# serialLogger.net
KiCad netlist of a schematic drawn in EAGLE
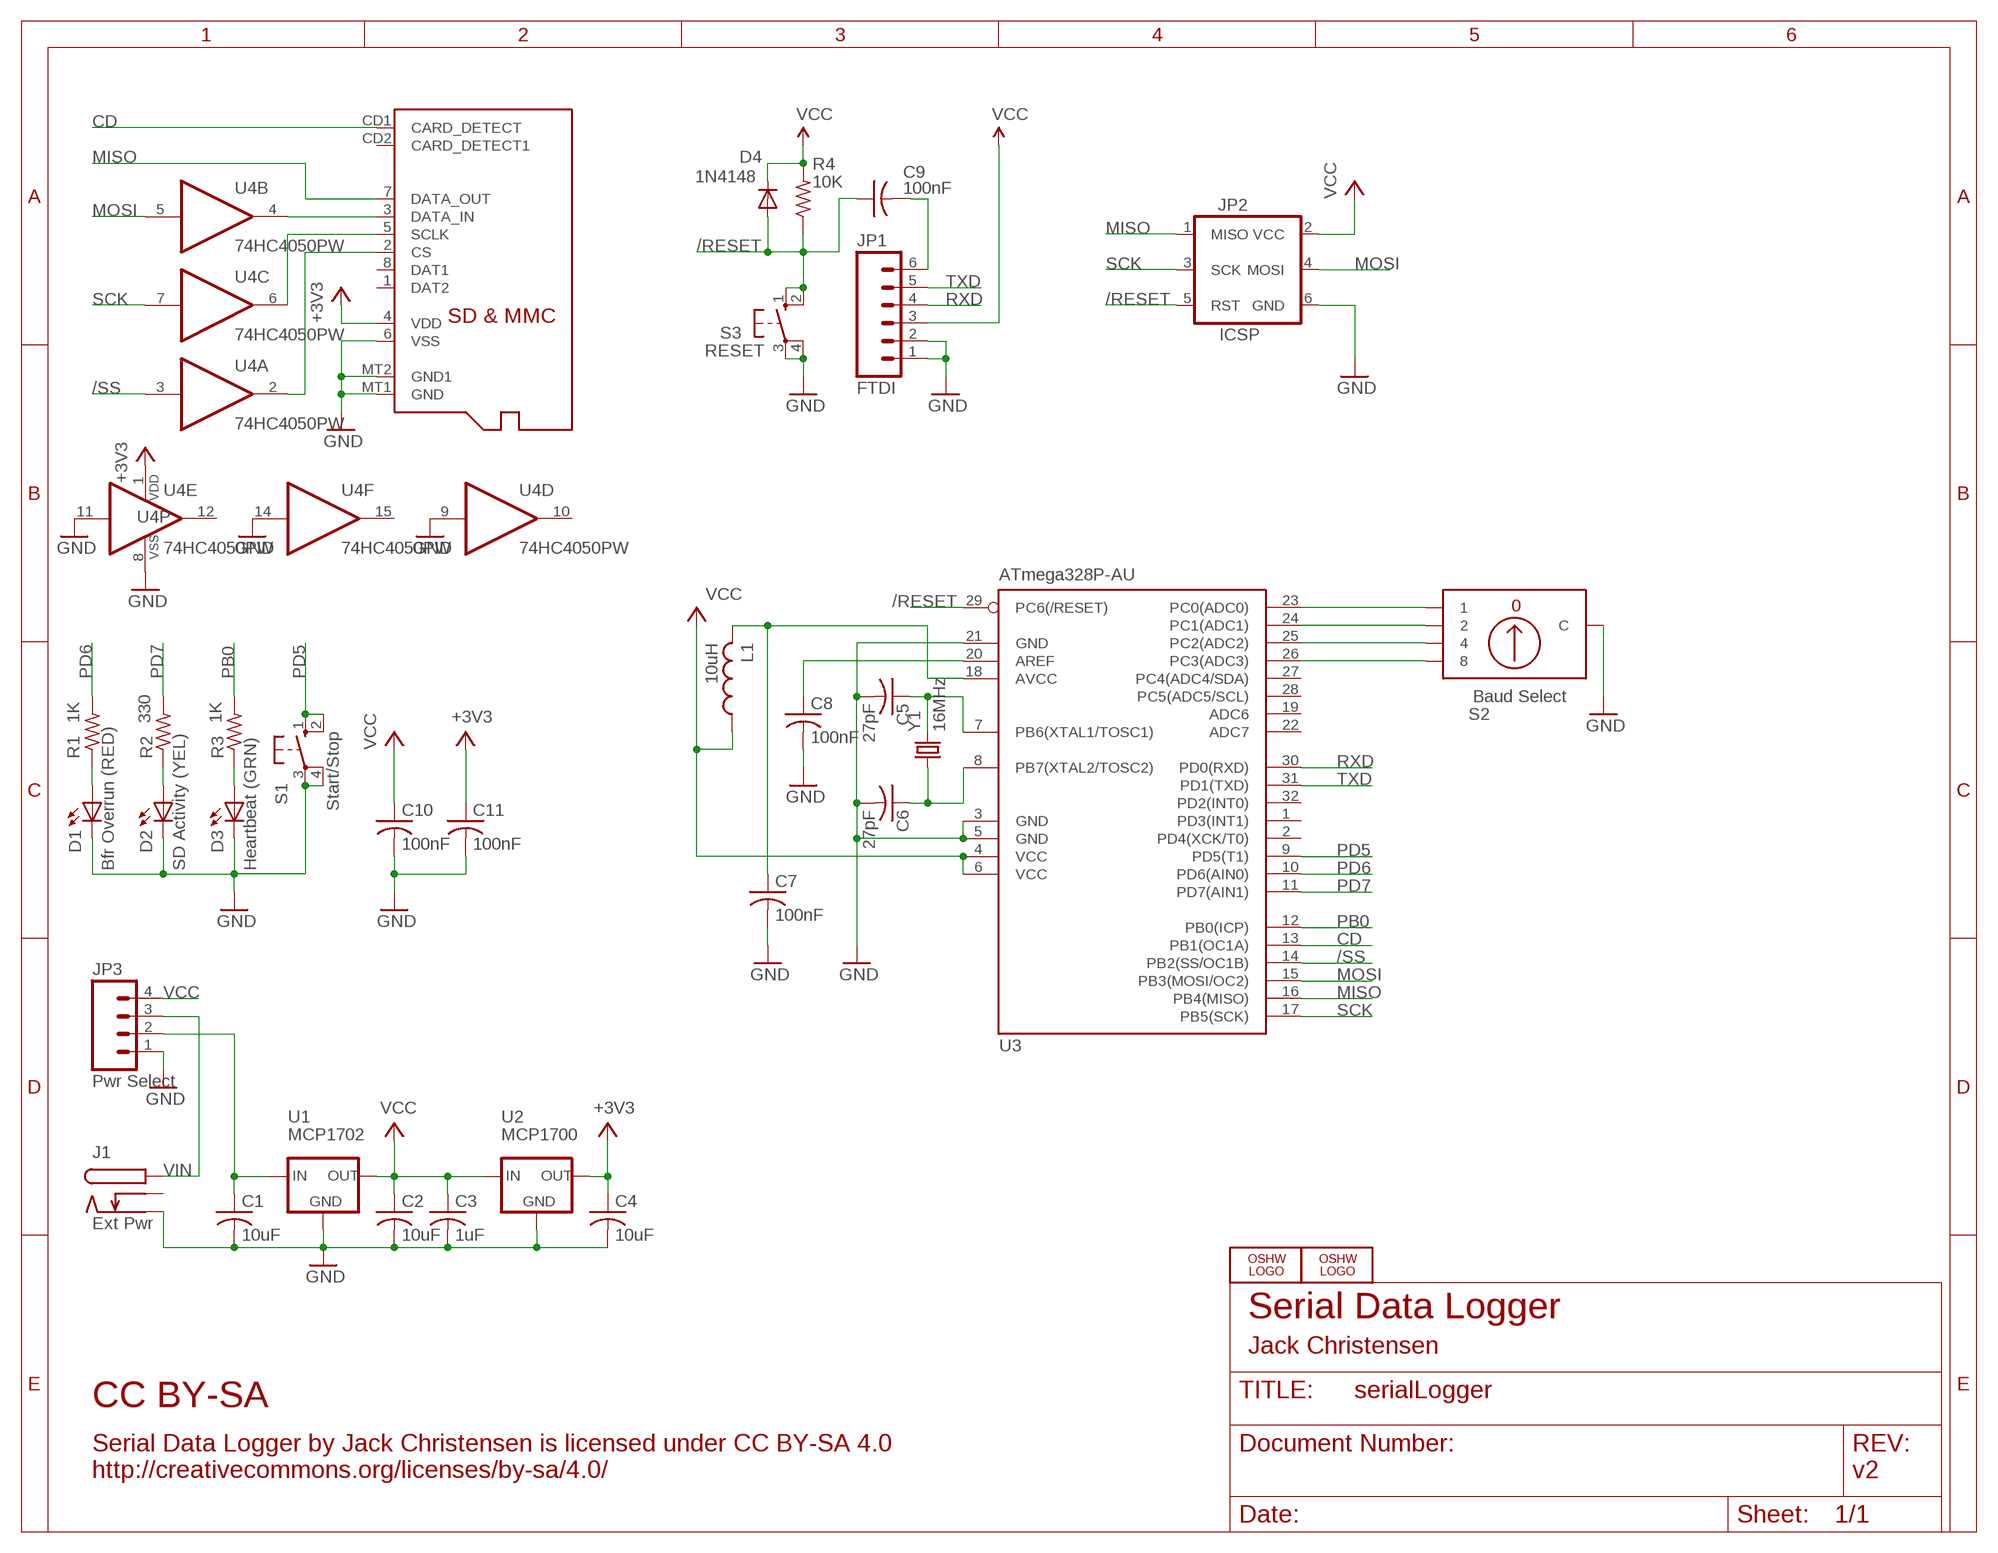
[diagram p0: schematic, sheet 1]

(export (version "E")
  (design (tool "Eeschema 10.0.6"))
  (components
    (comp (ref "C1")
      (value "10uF")
      (footprint "eagle-import:M0805")
      (libsource (lib "eagle-import") (part "C-USM0805"))
    )
    (comp (ref "C2")
      (value "10uF")
      (footprint "eagle-import:M0805")
      (libsource (lib "eagle-import") (part "C-USM0805"))
    )
    (comp (ref "C3")
      (value "1uF")
      (footprint "eagle-import:M0805")
      (libsource (lib "eagle-import") (part "C-USM0805"))
    )
    (comp (ref "C4")
      (value "10uF")
      (footprint "eagle-import:M0805")
      (libsource (lib "eagle-import") (part "C-USM0805"))
    )
    (comp (ref "C5")
      (value "27pF")
      (footprint "eagle-import:M0805")
      (libsource (lib "eagle-import") (part "C-USM0805"))
    )
    (comp (ref "C6")
      (value "27pF")
      (footprint "eagle-import:M0805")
      (libsource (lib "eagle-import") (part "C-USM0805"))
    )
    (comp (ref "C7")
      (value "100nF")
      (footprint "eagle-import:M0805")
      (libsource (lib "eagle-import") (part "C-USM0805"))
    )
    (comp (ref "C8")
      (value "100nF")
      (footprint "eagle-import:M0805")
      (libsource (lib "eagle-import") (part "C-USM0805"))
    )
    (comp (ref "C9")
      (value "100nF")
      (footprint "eagle-import:M0805")
      (libsource (lib "eagle-import") (part "C-USM0805"))
    )
    (comp (ref "C10")
      (value "100nF")
      (footprint "eagle-import:M0805")
      (libsource (lib "eagle-import") (part "C-USM0805"))
    )
    (comp (ref "C11")
      (value "100nF")
      (footprint "eagle-import:M0805")
      (libsource (lib "eagle-import") (part "C-USM0805"))
    )
    (comp (ref "D1")
      (value "Bfr Overrun (RED)")
      (footprint "eagle-import:CHIPLED_1206")
      (libsource (lib "eagle-import") (part "LEDCHIPLED_1206"))
    )
    (comp (ref "D2")
      (value "SD Activity (YEL)")
      (footprint "eagle-import:CHIPLED_1206")
      (libsource (lib "eagle-import") (part "LEDCHIPLED_1206"))
    )
    (comp (ref "D3")
      (value "Heartbeat (GRN)")
      (footprint "eagle-import:CHIPLED_1206")
      (libsource (lib "eagle-import") (part "LEDCHIPLED_1206"))
    )
    (comp (ref "D4")
      (value "1N4148")
      (footprint "eagle-import:SOD-323F-A")
      (libsource (lib "eagle-import") (part "DIODESOD-323F-A"))
    )
    (comp (ref "J1")
      (value "Ext Pwr")
      (footprint "eagle-import:KLDX-0202")
      (libsource (lib "eagle-import") (part "POWER-JACK"))
    )
    (comp (ref "JP1")
      (value "FTDI")
      (footprint "eagle-import:1X06_LOCK")
      (libsource (lib "eagle-import") (part "M06LOCK"))
    )
    (comp (ref "JP2")
      (value "ICSP")
      (footprint "eagle-import:2X3_LOCK")
      (libsource (lib "eagle-import") (part "AVR_SPI_PRG_62X3_LOCK"))
    )
    (comp (ref "JP3")
      (value "Pwr Select")
      (footprint "eagle-import:1X04_LOCK")
      (libsource (lib "eagle-import") (part "M04LOCK"))
    )
    (comp (ref "L1")
      (value "10uH")
      (footprint "eagle-import:M0805")
      (libsource (lib "eagle-import") (part "INDUCTORM0805"))
    )
    (comp (ref "LOGO1")
      (value "OSHW_LOGO_10MILX0200-NT")
      (footprint "eagle-import:OSHW_10X200_NOTEXT")
      (libsource (lib "eagle-import") (part "OSHW_LOGO_10MILX0200-NT"))
    )
    (comp (ref "LOGO2")
      (value "OSHW_LOGO_10MILX0200-NT")
      (footprint "eagle-import:OSHW_10X200_NOTEXT")
      (libsource (lib "eagle-import") (part "OSHW_LOGO_10MILX0200-NT"))
    )
    (comp (ref "R1")
      (value "1K")
      (footprint "eagle-import:M0805")
      (libsource (lib "eagle-import") (part "R-US_M0805"))
    )
    (comp (ref "R2")
      (value "330")
      (footprint "eagle-import:M0805")
      (libsource (lib "eagle-import") (part "R-US_M0805"))
    )
    (comp (ref "R3")
      (value "1K")
      (footprint "eagle-import:M0805")
      (libsource (lib "eagle-import") (part "R-US_M0805"))
    )
    (comp (ref "R4")
      (value "10K")
      (footprint "eagle-import:M0805")
      (libsource (lib "eagle-import") (part "R-US_M0805"))
    )
    (comp (ref "S1")
      (value "Start/Stop")
      (footprint "eagle-import:B3F-10XXOCT")
      (libsource (lib "eagle-import") (part "10-XXOCT"))
    )
    (comp (ref "S2")
      (value "Baud Select")
      (footprint "eagle-import:OMRON-A6RS-102")
      (libsource (lib "eagle-import") (part "OMRON-A6RS-102"))
    )
    (comp (ref "S3")
      (value "RESET")
      (footprint "eagle-import:B3F-10XXOCT")
      (libsource (lib "eagle-import") (part "10-XXOCT"))
    )
    (comp (ref "U1")
      (value "MCP1702")
      (footprint "eagle-import:SOT89")
      (libsource (lib "eagle-import") (part "MCP1700SOT89"))
    )
    (comp (ref "U2")
      (value "MCP1700")
      (footprint "eagle-import:SOT23")
      (libsource (lib "eagle-import") (part "MCP1700SOT23"))
    )
    (comp (ref "U3")
      (value "ATmega328P-AU")
      (footprint "eagle-import:TQFP32-08")
      (fields (field (name "MPN") "ATMEGA8-16AU"))
      (libsource (lib "eagle-import") (part "MEGA8-AI"))
    )
    (comp (ref "U4")
      (value "74HC4050PW")
      (footprint "eagle-import:TSSOP16")
      (libsource (lib "eagle-import") (part "4050PW"))
    )
    (comp (ref "X1")
      (value "MICROSD")
      (footprint "eagle-import:MICROSD")
      (libsource (lib "eagle-import") (part "MICROSD"))
    )
    (comp (ref "Y1")
      (value "16MHz")
      (footprint "eagle-import:CRYSTAL-ABRACON-ABM2")
      (libsource (lib "eagle-import") (part "CRYSTALABM2"))
    )
  )
  (nets
    (net (code "1") (name "+3V3") (class "Default")
      (node (ref "C11") (pin "1") (pinfunction "1_1") (pintype "passive"))
      (node (ref "C4") (pin "1") (pinfunction "1_1") (pintype "passive"))
      (node (ref "U2") (pin "2") (pinfunction "OUT_2") (pintype "passive"))
      (node (ref "U4") (pin "1") (pinfunction "VDD_1") (pintype "power_in"))
      (node (ref "X1") (pin "4") (pinfunction "VDD_4") (pintype "power_in"))
    )
    (net (code "2") (name "/CD") (class "Default")
      (node (ref "U3") (pin "13") (pinfunction "PB1(OC1A)_13") (pintype "bidirectional"))
      (node (ref "X1") (pin "CD1") (pinfunction "CARD_DETECT_CD1") (pintype "passive"))
    )
    (net (code "3") (name "/MISO") (class "Default")
      (node (ref "JP2") (pin "1") (pinfunction "MISO_1") (pintype "passive"))
      (node (ref "U3") (pin "16") (pinfunction "PB4(MISO)_16") (pintype "bidirectional"))
      (node (ref "X1") (pin "7") (pinfunction "DATA_OUT_7") (pintype "output"))
    )
    (net (code "4") (name "/MOSI") (class "Default")
      (node (ref "JP2") (pin "4") (pinfunction "MOSI_4") (pintype "passive"))
      (node (ref "U3") (pin "15") (pinfunction "PB3(MOSI/OC2)_15") (pintype "bidirectional"))
      (node (ref "U4") (pin "5") (pinfunction "I_5") (pintype "input"))
    )
    (net (code "5") (name "/PB0") (class "Default")
      (node (ref "R3") (pin "2") (pinfunction "2_2") (pintype "passive"))
      (node (ref "U3") (pin "12") (pinfunction "PB0(ICP)_12") (pintype "bidirectional"))
    )
    (net (code "6") (name "/PD5") (class "Default")
      (node (ref "S1") (pin "1") (pinfunction "S_1") (pintype "passive"))
      (node (ref "S1") (pin "2") (pinfunction "S1_2") (pintype "passive"))
      (node (ref "U3") (pin "9") (pinfunction "PD5(T1)_9") (pintype "bidirectional"))
    )
    (net (code "7") (name "/PD6") (class "Default")
      (node (ref "R1") (pin "2") (pinfunction "2_2") (pintype "passive"))
      (node (ref "U3") (pin "10") (pinfunction "PD6(AIN0)_10") (pintype "bidirectional"))
    )
    (net (code "8") (name "/PD7") (class "Default")
      (node (ref "R2") (pin "2") (pinfunction "2_2") (pintype "passive"))
      (node (ref "U3") (pin "11") (pinfunction "PD7(AIN1)_11") (pintype "bidirectional"))
    )
    (net (code "9") (name "/RXD") (class "Default")
      (node (ref "JP1") (pin "4") (pinfunction "4_4") (pintype "passive"))
      (node (ref "U3") (pin "30") (pinfunction "PD0(RXD)_30") (pintype "bidirectional"))
    )
    (net (code "10") (name "/SCK") (class "Default")
      (node (ref "JP2") (pin "3") (pinfunction "SCK_3") (pintype "passive"))
      (node (ref "U3") (pin "17") (pinfunction "PB5(SCK)_17") (pintype "bidirectional"))
      (node (ref "U4") (pin "7") (pinfunction "I_7") (pintype "input"))
    )
    (net (code "11") (name "/TXD") (class "Default")
      (node (ref "JP1") (pin "5") (pinfunction "5_5") (pintype "passive"))
      (node (ref "U3") (pin "31") (pinfunction "PD1(TXD)_31") (pintype "bidirectional"))
    )
    (net (code "12") (name "/VIN") (class "Default")
      (node (ref "J1") (pin "P$1") (pinfunction "P$1_P$1") (pintype "bidirectional"))
      (node (ref "JP3") (pin "3") (pinfunction "3_3") (pintype "passive"))
    )
    (net (code "13") (name "/{slash}RESET") (class "Default")
      (node (ref "C9") (pin "1") (pinfunction "1_1") (pintype "passive"))
      (node (ref "D4") (pin "A") (pinfunction "A_A") (pintype "passive"))
      (node (ref "JP2") (pin "5") (pinfunction "RST_5") (pintype "passive"))
      (node (ref "R4") (pin "1") (pinfunction "1_1") (pintype "passive"))
      (node (ref "S3") (pin "1") (pinfunction "S_1") (pintype "passive"))
      (node (ref "S3") (pin "2") (pinfunction "S1_2") (pintype "passive"))
      (node (ref "U3") (pin "29") (pinfunction "PC6(/RESET)_29") (pintype "bidirectional"))
    )
    (net (code "14") (name "/{slash}SS") (class "Default")
      (node (ref "U3") (pin "14") (pinfunction "PB2(SS/OC1B)_14") (pintype "bidirectional"))
      (node (ref "U4") (pin "3") (pinfunction "I_3") (pintype "input"))
    )
    (net (code "15") (name "GND") (class "Default")
      (node (ref "C1") (pin "2") (pinfunction "2_2") (pintype "passive"))
      (node (ref "C10") (pin "2") (pinfunction "2_2") (pintype "passive"))
      (node (ref "C11") (pin "2") (pinfunction "2_2") (pintype "passive"))
      (node (ref "C2") (pin "2") (pinfunction "2_2") (pintype "passive"))
      (node (ref "C3") (pin "2") (pinfunction "2_2") (pintype "passive"))
      (node (ref "C4") (pin "2") (pinfunction "2_2") (pintype "passive"))
      (node (ref "C5") (pin "2") (pinfunction "2_2") (pintype "passive"))
      (node (ref "C6") (pin "2") (pinfunction "2_2") (pintype "passive"))
      (node (ref "C7") (pin "2") (pinfunction "2_2") (pintype "passive"))
      (node (ref "C8") (pin "2") (pinfunction "2_2") (pintype "passive"))
      (node (ref "D1") (pin "C") (pinfunction "C_C") (pintype "passive"))
      (node (ref "D2") (pin "C") (pinfunction "C_C") (pintype "passive"))
      (node (ref "D3") (pin "C") (pinfunction "C_C") (pintype "passive"))
      (node (ref "J1") (pin "P$2") (pinfunction "P$2_P$2") (pintype "bidirectional"))
      (node (ref "JP1") (pin "1") (pinfunction "1_1") (pintype "passive"))
      (node (ref "JP1") (pin "2") (pinfunction "2_2") (pintype "passive"))
      (node (ref "JP2") (pin "6") (pinfunction "GND_6") (pintype "passive"))
      (node (ref "JP3") (pin "1") (pinfunction "1_1") (pintype "passive"))
      (node (ref "S1") (pin "3") (pinfunction "P_3") (pintype "passive"))
      (node (ref "S1") (pin "4") (pinfunction "P1_4") (pintype "passive"))
      (node (ref "S2") (pin "C.1") (pinfunction "C_C.1") (pintype "bidirectional"))
      (node (ref "S2") (pin "C.2") (pinfunction "C_C.2") (pintype "bidirectional"))
      (node (ref "S3") (pin "3") (pinfunction "P_3") (pintype "passive"))
      (node (ref "S3") (pin "4") (pinfunction "P1_4") (pintype "passive"))
      (node (ref "U1") (pin "1") (pinfunction "GND_1") (pintype "input"))
      (node (ref "U2") (pin "1") (pinfunction "GND_1") (pintype "input"))
      (node (ref "U3") (pin "21") (pinfunction "GND_21") (pintype "power_in"))
      (node (ref "U3") (pin "3") (pinfunction "GND_3") (pintype "power_in"))
      (node (ref "U3") (pin "5") (pinfunction "GND_5") (pintype "power_in"))
      (node (ref "U4") (pin "11") (pinfunction "I_11") (pintype "input"))
      (node (ref "U4") (pin "14") (pinfunction "I_14") (pintype "input"))
      (node (ref "U4") (pin "8") (pinfunction "VSS_8") (pintype "power_in"))
      (node (ref "U4") (pin "9") (pinfunction "I_9") (pintype "input"))
      (node (ref "X1") (pin "6") (pinfunction "VSS_6") (pintype "power_in"))
      (node (ref "X1") (pin "MT1") (pinfunction "GND_MT1") (pintype "power_in"))
      (node (ref "X1") (pin "MT2") (pinfunction "GND1_MT2") (pintype "power_in"))
    )
    (net (code "16") (name "Net-(C1-Pad1)") (class "Default")
      (node (ref "C1") (pin "1") (pinfunction "1_1") (pintype "passive"))
      (node (ref "JP3") (pin "2") (pinfunction "2_2") (pintype "passive"))
      (node (ref "U1") (pin "2") (pinfunction "IN_2") (pintype "input"))
      (node (ref "U1") (pin "2.1") (pinfunction "IN_2.1") (pintype "input"))
    )
    (net (code "17") (name "Net-(C9-Pad2)") (class "Default")
      (node (ref "C9") (pin "2") (pinfunction "2_2") (pintype "passive"))
      (node (ref "JP1") (pin "6") (pinfunction "6_6") (pintype "passive"))
    )
    (net (code "18") (name "Net-(D1-PadA)") (class "Default")
      (node (ref "D1") (pin "A") (pinfunction "A_A") (pintype "passive"))
      (node (ref "R1") (pin "1") (pinfunction "1_1") (pintype "passive"))
    )
    (net (code "19") (name "Net-(D2-PadA)") (class "Default")
      (node (ref "D2") (pin "A") (pinfunction "A_A") (pintype "passive"))
      (node (ref "R2") (pin "1") (pinfunction "1_1") (pintype "passive"))
    )
    (net (code "20") (name "Net-(D3-PadA)") (class "Default")
      (node (ref "D3") (pin "A") (pinfunction "A_A") (pintype "passive"))
      (node (ref "R3") (pin "1") (pinfunction "1_1") (pintype "passive"))
    )
    (net (code "21") (name "Net-(U3-AREF)") (class "Default")
      (node (ref "C8") (pin "1") (pinfunction "1_1") (pintype "passive"))
      (node (ref "U3") (pin "20") (pinfunction "AREF_20") (pintype "passive"))
    )
    (net (code "22") (name "Net-(U3-AVCC)") (class "Default")
      (node (ref "C7") (pin "1") (pinfunction "1_1") (pintype "passive"))
      (node (ref "L1") (pin "2") (pinfunction "2_2") (pintype "passive"))
      (node (ref "U3") (pin "18") (pinfunction "AVCC_18") (pintype "power_in"))
    )
    (net (code "23") (name "Net-(U3-PB6(XTAL1{slash}TOSC1))") (class "Default")
      (node (ref "C5") (pin "1") (pinfunction "1_1") (pintype "passive"))
      (node (ref "U3") (pin "7") (pinfunction "PB6(XTAL1/TOSC1)_7") (pintype "bidirectional"))
      (node (ref "Y1") (pin "P$2") (pinfunction "2_P$2") (pintype "passive"))
    )
    (net (code "24") (name "Net-(U3-PB7(XTAL2{slash}TOSC2))") (class "Default")
      (node (ref "C6") (pin "1") (pinfunction "1_1") (pintype "passive"))
      (node (ref "U3") (pin "8") (pinfunction "PB7(XTAL2/TOSC2)_8") (pintype "bidirectional"))
      (node (ref "Y1") (pin "P$1") (pinfunction "1_P$1") (pintype "passive"))
    )
    (net (code "25") (name "Net-(U3-PC0(ADC0))") (class "Default")
      (node (ref "S2") (pin "1") (pinfunction "1_1") (pintype "bidirectional"))
      (node (ref "U3") (pin "23") (pinfunction "PC0(ADC0)_23") (pintype "bidirectional"))
    )
    (net (code "26") (name "Net-(U3-PC1(ADC1))") (class "Default")
      (node (ref "S2") (pin "2") (pinfunction "2_2") (pintype "bidirectional"))
      (node (ref "U3") (pin "24") (pinfunction "PC1(ADC1)_24") (pintype "bidirectional"))
    )
    (net (code "27") (name "Net-(U3-PC2(ADC2))") (class "Default")
      (node (ref "S2") (pin "4") (pinfunction "4_4") (pintype "bidirectional"))
      (node (ref "U3") (pin "25") (pinfunction "PC2(ADC2)_25") (pintype "bidirectional"))
    )
    (net (code "28") (name "Net-(U3-PC3(ADC3))") (class "Default")
      (node (ref "S2") (pin "8") (pinfunction "8_8") (pintype "bidirectional"))
      (node (ref "U3") (pin "26") (pinfunction "PC3(ADC3)_26") (pintype "bidirectional"))
    )
    (net (code "29") (name "Net-(U4A-O)") (class "Default")
      (node (ref "U4") (pin "2") (pinfunction "O_2") (pintype "output"))
      (node (ref "X1") (pin "2") (pinfunction "CS_2") (pintype "input"))
    )
    (net (code "30") (name "Net-(U4B-O)") (class "Default")
      (node (ref "U4") (pin "4") (pinfunction "O_4") (pintype "output"))
      (node (ref "X1") (pin "3") (pinfunction "DATA_IN_3") (pintype "input"))
    )
    (net (code "31") (name "Net-(U4C-O)") (class "Default")
      (node (ref "U4") (pin "6") (pinfunction "O_6") (pintype "output"))
      (node (ref "X1") (pin "5") (pinfunction "SCLK_5") (pintype "input"))
    )
    (net (code "32") (name "VCC") (class "Default")
      (node (ref "C10") (pin "1") (pinfunction "1_1") (pintype "passive"))
      (node (ref "C2") (pin "1") (pinfunction "1_1") (pintype "passive"))
      (node (ref "C3") (pin "1") (pinfunction "1_1") (pintype "passive"))
      (node (ref "D4") (pin "K") (pinfunction "K_K") (pintype "passive"))
      (node (ref "JP1") (pin "3") (pinfunction "3_3") (pintype "passive"))
      (node (ref "JP2") (pin "2") (pinfunction "VCC_2") (pintype "passive"))
      (node (ref "JP3") (pin "4") (pinfunction "4_4") (pintype "passive"))
      (node (ref "L1") (pin "1") (pinfunction "1_1") (pintype "passive"))
      (node (ref "R4") (pin "2") (pinfunction "2_2") (pintype "passive"))
      (node (ref "U1") (pin "3") (pinfunction "OUT_3") (pintype "passive"))
      (node (ref "U2") (pin "3") (pinfunction "IN_3") (pintype "input"))
      (node (ref "U3") (pin "4") (pinfunction "VCC_4") (pintype "power_in"))
      (node (ref "U3") (pin "6") (pinfunction "VCC_6") (pintype "power_in"))
    )
    (net (code "33") (name "unconnected-(J1-PadP$3)") (class "Default")
      (node (ref "J1") (pin "P$3") (pinfunction "P$3_P$3") (pintype "bidirectional"))
    )
    (net (code "34") (name "unconnected-(U3-ADC6-Pad19)") (class "Default")
      (node (ref "U3") (pin "19") (pinfunction "ADC6_19") (pintype "bidirectional"))
    )
    (net (code "35") (name "unconnected-(U3-ADC7-Pad22)") (class "Default")
      (node (ref "U3") (pin "22") (pinfunction "ADC7_22") (pintype "bidirectional"))
    )
    (net (code "36") (name "unconnected-(U3-PC4(ADC4{slash}SDA)-Pad27)") (class "Default")
      (node (ref "U3") (pin "27") (pinfunction "PC4(ADC4/SDA)_27") (pintype "bidirectional"))
    )
    (net (code "37") (name "unconnected-(U3-PC5(ADC5{slash}SCL)-Pad28)") (class "Default")
      (node (ref "U3") (pin "28") (pinfunction "PC5(ADC5/SCL)_28") (pintype "bidirectional"))
    )
    (net (code "38") (name "unconnected-(U3-PD2(INT0)-Pad32)") (class "Default")
      (node (ref "U3") (pin "32") (pinfunction "PD2(INT0)_32") (pintype "bidirectional"))
    )
    (net (code "39") (name "unconnected-(U3-PD3(INT1)-Pad1)") (class "Default")
      (node (ref "U3") (pin "1") (pinfunction "PD3(INT1)_1") (pintype "bidirectional"))
    )
    (net (code "40") (name "unconnected-(U3-PD4(XCK{slash}T0)-Pad2)") (class "Default")
      (node (ref "U3") (pin "2") (pinfunction "PD4(XCK/T0)_2") (pintype "bidirectional"))
    )
    (net (code "41") (name "unconnected-(U4D-O-Pad10)") (class "Default")
      (node (ref "U4") (pin "10") (pinfunction "O_10") (pintype "output"))
    )
    (net (code "42") (name "unconnected-(U4E-O-Pad12)") (class "Default")
      (node (ref "U4") (pin "12") (pinfunction "O_12") (pintype "output"))
    )
    (net (code "43") (name "unconnected-(U4F-O-Pad15)") (class "Default")
      (node (ref "U4") (pin "15") (pinfunction "O_15") (pintype "output"))
    )
    (net (code "44") (name "unconnected-(X1-CARD_DETECT1-PadCD2)") (class "Default")
      (node (ref "X1") (pin "CD2") (pinfunction "CARD_DETECT1_CD2") (pintype "passive"))
    )
    (net (code "45") (name "unconnected-(X1-DAT1-Pad8)") (class "Default")
      (node (ref "X1") (pin "8") (pinfunction "DAT1_8") (pintype "bidirectional"))
    )
    (net (code "46") (name "unconnected-(X1-DAT2-Pad1)") (class "Default")
      (node (ref "X1") (pin "1") (pinfunction "DAT2_1") (pintype "bidirectional"))
    )
  )
)
